# TripleCtrl.net
KiCad netlist of a schematic drawn in EAGLE
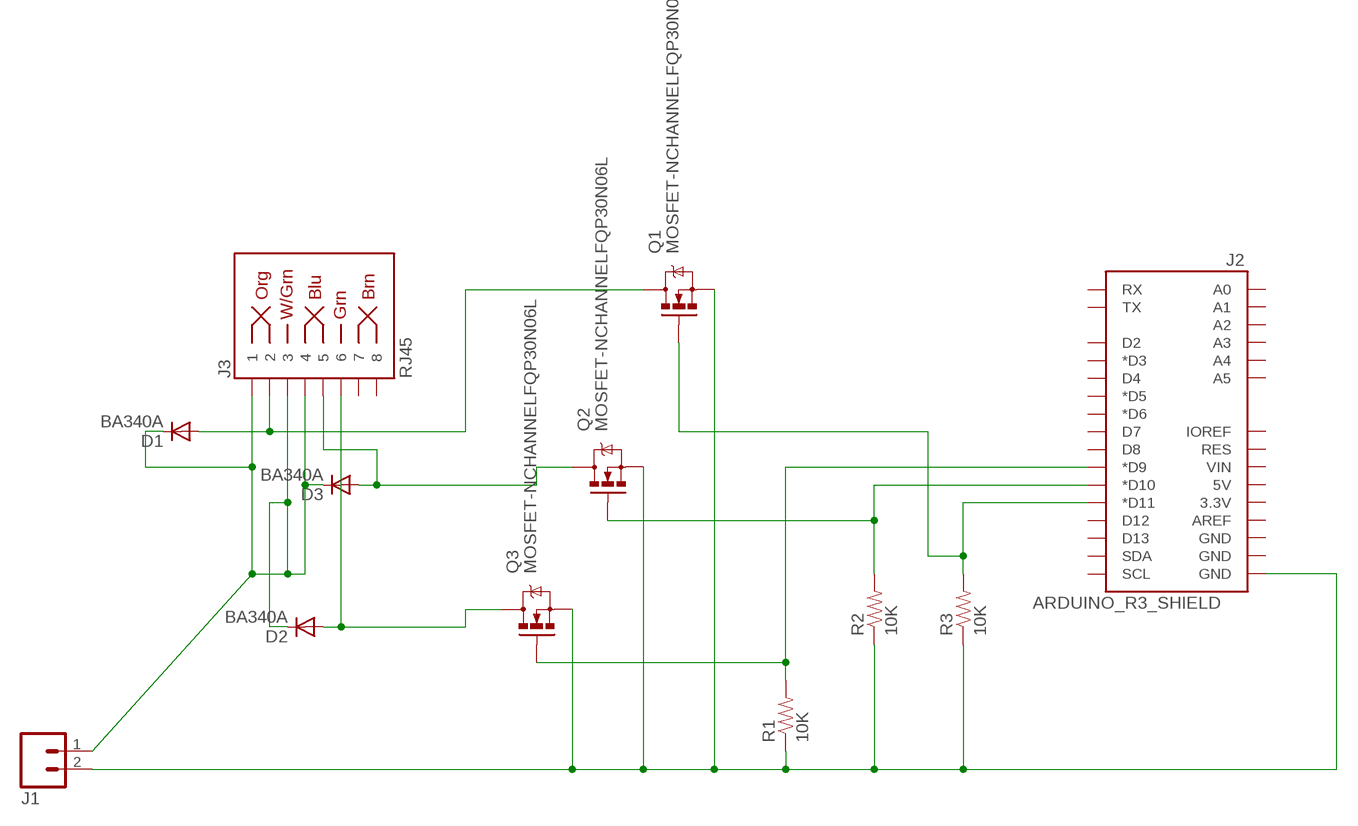
[diagram p0: schematic, sheet 1]

(export (version "E")
  (design (tool "Eeschema 10.0.6"))
  (components
    (comp (ref "D1")
      (value "BA340A")
      (footprint "eagle-import:DO41-10")
      (libsource (lib "eagle-import") (part "1N4004"))
    )
    (comp (ref "D2")
      (value "BA340A")
      (footprint "eagle-import:DO41-10")
      (libsource (lib "eagle-import") (part "1N4004"))
    )
    (comp (ref "D3")
      (value "BA340A")
      (footprint "eagle-import:DO41-10")
      (libsource (lib "eagle-import") (part "1N4004"))
    )
    (comp (ref "J1")
      (value "M025MM")
      (footprint "eagle-import:SCREWTERMINAL-5MM-2")
      (libsource (lib "eagle-import") (part "M025MM"))
    )
    (comp (ref "J2")
      (value "ARDUINO_R3_SHIELD")
      (footprint "eagle-import:UNO_R3_SHIELD")
      (libsource (lib "eagle-import") (part "ARDUINO_R3_SHIELD"))
    )
    (comp (ref "J3")
      (value "RJ45")
      (footprint "eagle-import:RJ45-8")
      (libsource (lib "eagle-import") (part "RJ45-8PTH"))
    )
    (comp (ref "Q1")
      (value "MOSFET-NCHANNELFQP30N06L")
      (footprint "eagle-import:TO220V")
      (libsource (lib "eagle-import") (part "MOSFET-NCHANNELFQP30N06L"))
    )
    (comp (ref "Q2")
      (value "MOSFET-NCHANNELFQP30N06L")
      (footprint "eagle-import:TO220V")
      (libsource (lib "eagle-import") (part "MOSFET-NCHANNELFQP30N06L"))
    )
    (comp (ref "Q3")
      (value "MOSFET-NCHANNELFQP30N06L")
      (footprint "eagle-import:TO220V")
      (libsource (lib "eagle-import") (part "MOSFET-NCHANNELFQP30N06L"))
    )
    (comp (ref "R1")
      (value "10K")
      (footprint "eagle-import:AXIAL-0.3-KIT")
      (libsource (lib "eagle-import") (part "10KOHM-1/6W-5%(PTH)KIT"))
    )
    (comp (ref "R2")
      (value "10K")
      (footprint "eagle-import:AXIAL-0.3-KIT")
      (libsource (lib "eagle-import") (part "10KOHM-1/6W-5%(PTH)KIT"))
    )
    (comp (ref "R3")
      (value "10K")
      (footprint "eagle-import:AXIAL-0.3-KIT")
      (libsource (lib "eagle-import") (part "10KOHM-1/6W-5%(PTH)KIT"))
    )
  )
  (nets
    (net (code "1") (name "Net-(D1-PadC)") (class "Default")
      (node (ref "D1") (pin "C") (pinfunction "C_C") (pintype "passive"))
      (node (ref "D2") (pin "C") (pinfunction "C_C") (pintype "passive"))
      (node (ref "D3") (pin "C") (pinfunction "C_C") (pintype "passive"))
      (node (ref "J1") (pin "1") (pinfunction "1_1") (pintype "passive"))
      (node (ref "J3") (pin "1") (pinfunction "1_1") (pintype "bidirectional"))
      (node (ref "J3") (pin "3") (pinfunction "3_3") (pintype "bidirectional"))
      (node (ref "J3") (pin "4") (pinfunction "4_4") (pintype "bidirectional"))
    )
    (net (code "2") (name "Net-(J2-*D9)") (class "Default")
      (node (ref "J2") (pin "D9") (pinfunction "*D9_D9") (pintype "bidirectional"))
      (node (ref "Q3") (pin "1") (pinfunction "G_1") (pintype "passive"))
      (node (ref "R1") (pin "P$2") (pinfunction "2_P$2") (pintype "passive"))
    )
    (net (code "3") (name "Net-(J2-*D10)") (class "Default")
      (node (ref "J2") (pin "D10") (pinfunction "*D10_D10") (pintype "bidirectional"))
      (node (ref "Q2") (pin "1") (pinfunction "G_1") (pintype "passive"))
      (node (ref "R2") (pin "P$2") (pinfunction "2_P$2") (pintype "passive"))
    )
    (net (code "4") (name "Net-(J2-*D11)") (class "Default")
      (node (ref "J2") (pin "D11") (pinfunction "*D11_D11") (pintype "bidirectional"))
      (node (ref "Q1") (pin "1") (pinfunction "G_1") (pintype "passive"))
      (node (ref "R3") (pin "P$2") (pinfunction "2_P$2") (pintype "passive"))
    )
    (net (code "5") (name "Net-(Q1-D)") (class "Default")
      (node (ref "D1") (pin "A") (pinfunction "A_A") (pintype "passive"))
      (node (ref "J3") (pin "2") (pinfunction "2_2") (pintype "bidirectional"))
      (node (ref "Q1") (pin "2") (pinfunction "D_2") (pintype "passive"))
    )
    (net (code "6") (name "Net-(Q1-S)") (class "Default")
      (node (ref "J1") (pin "2") (pinfunction "2_2") (pintype "passive"))
      (node (ref "J2") (pin "GND@0") (pinfunction "GND_GND@0") (pintype "bidirectional"))
      (node (ref "Q1") (pin "3") (pinfunction "S_3") (pintype "passive"))
      (node (ref "Q2") (pin "3") (pinfunction "S_3") (pintype "passive"))
      (node (ref "Q3") (pin "3") (pinfunction "S_3") (pintype "passive"))
      (node (ref "R1") (pin "P$1") (pinfunction "1_P$1") (pintype "passive"))
      (node (ref "R2") (pin "P$1") (pinfunction "1_P$1") (pintype "passive"))
      (node (ref "R3") (pin "P$1") (pinfunction "1_P$1") (pintype "passive"))
    )
    (net (code "7") (name "Net-(Q2-D)") (class "Default")
      (node (ref "D3") (pin "A") (pinfunction "A_A") (pintype "passive"))
      (node (ref "J3") (pin "5") (pinfunction "5_5") (pintype "bidirectional"))
      (node (ref "Q2") (pin "2") (pinfunction "D_2") (pintype "passive"))
    )
    (net (code "8") (name "Net-(Q3-D)") (class "Default")
      (node (ref "D2") (pin "A") (pinfunction "A_A") (pintype "passive"))
      (node (ref "J3") (pin "6") (pinfunction "6_6") (pintype "bidirectional"))
      (node (ref "Q3") (pin "2") (pinfunction "D_2") (pintype "passive"))
    )
    (net (code "9") (name "unconnected-(J2-*D3-PadD3)") (class "Default")
      (node (ref "J2") (pin "D3") (pinfunction "*D3_D3") (pintype "bidirectional"))
    )
    (net (code "10") (name "unconnected-(J2-*D5-PadD5)") (class "Default")
      (node (ref "J2") (pin "D5") (pinfunction "*D5_D5") (pintype "bidirectional"))
    )
    (net (code "11") (name "unconnected-(J2-*D6-PadD6)") (class "Default")
      (node (ref "J2") (pin "D6") (pinfunction "*D6_D6") (pintype "bidirectional"))
    )
    (net (code "12") (name "unconnected-(J2-GND-PadGND@1)") (class "Default")
      (node (ref "J2") (pin "GND@1") (pinfunction "GND_GND@1") (pintype "bidirectional"))
    )
    (net (code "13") (name "unconnected-(J2-GND-PadGND@2)") (class "Default")
      (node (ref "J2") (pin "GND@2") (pinfunction "GND_GND@2") (pintype "bidirectional"))
    )
    (net (code "14") (name "unconnected-(J2-Pad3.3V)") (class "Default")
      (node (ref "J2") (pin "3.3V") (pinfunction "3.3V_3.3V") (pintype "bidirectional"))
    )
    (net (code "15") (name "unconnected-(J2-Pad5V)") (class "Default")
      (node (ref "J2") (pin "5V") (pinfunction "5V_5V") (pintype "bidirectional"))
    )
    (net (code "16") (name "unconnected-(J2-PadA0)") (class "Default")
      (node (ref "J2") (pin "A0") (pinfunction "A0_A0") (pintype "bidirectional"))
    )
    (net (code "17") (name "unconnected-(J2-PadA1)") (class "Default")
      (node (ref "J2") (pin "A1") (pinfunction "A1_A1") (pintype "bidirectional"))
    )
    (net (code "18") (name "unconnected-(J2-PadA2)") (class "Default")
      (node (ref "J2") (pin "A2") (pinfunction "A2_A2") (pintype "bidirectional"))
    )
    (net (code "19") (name "unconnected-(J2-PadA3)") (class "Default")
      (node (ref "J2") (pin "A3") (pinfunction "A3_A3") (pintype "bidirectional"))
    )
    (net (code "20") (name "unconnected-(J2-PadA4)") (class "Default")
      (node (ref "J2") (pin "A4") (pinfunction "A4_A4") (pintype "bidirectional"))
    )
    (net (code "21") (name "unconnected-(J2-PadA5)") (class "Default")
      (node (ref "J2") (pin "A5") (pinfunction "A5_A5") (pintype "bidirectional"))
    )
    (net (code "22") (name "unconnected-(J2-PadAREF)") (class "Default")
      (node (ref "J2") (pin "AREF") (pinfunction "AREF_AREF") (pintype "bidirectional"))
    )
    (net (code "23") (name "unconnected-(J2-PadD2)") (class "Default")
      (node (ref "J2") (pin "D2") (pinfunction "D2_D2") (pintype "bidirectional"))
    )
    (net (code "24") (name "unconnected-(J2-PadD4)") (class "Default")
      (node (ref "J2") (pin "D4") (pinfunction "D4_D4") (pintype "bidirectional"))
    )
    (net (code "25") (name "unconnected-(J2-PadD7)") (class "Default")
      (node (ref "J2") (pin "D7") (pinfunction "D7_D7") (pintype "bidirectional"))
    )
    (net (code "26") (name "unconnected-(J2-PadD8)") (class "Default")
      (node (ref "J2") (pin "D8") (pinfunction "D8_D8") (pintype "bidirectional"))
    )
    (net (code "27") (name "unconnected-(J2-PadD12)") (class "Default")
      (node (ref "J2") (pin "D12") (pinfunction "D12_D12") (pintype "bidirectional"))
    )
    (net (code "28") (name "unconnected-(J2-PadD13)") (class "Default")
      (node (ref "J2") (pin "D13") (pinfunction "D13_D13") (pintype "bidirectional"))
    )
    (net (code "29") (name "unconnected-(J2-PadIOREF)") (class "Default")
      (node (ref "J2") (pin "IOREF") (pinfunction "IOREF_IOREF") (pintype "bidirectional"))
    )
    (net (code "30") (name "unconnected-(J2-PadRES)") (class "Default")
      (node (ref "J2") (pin "RES") (pinfunction "RES_RES") (pintype "bidirectional"))
    )
    (net (code "31") (name "unconnected-(J2-PadRX)") (class "Default")
      (node (ref "J2") (pin "RX") (pinfunction "RX_RX") (pintype "bidirectional"))
    )
    (net (code "32") (name "unconnected-(J2-PadSCL)") (class "Default")
      (node (ref "J2") (pin "SCL") (pinfunction "SCL_SCL") (pintype "bidirectional"))
    )
    (net (code "33") (name "unconnected-(J2-PadSDA)") (class "Default")
      (node (ref "J2") (pin "SDA") (pinfunction "SDA_SDA") (pintype "bidirectional"))
    )
    (net (code "34") (name "unconnected-(J2-PadTX)") (class "Default")
      (node (ref "J2") (pin "TX") (pinfunction "TX_TX") (pintype "bidirectional"))
    )
    (net (code "35") (name "unconnected-(J2-PadVIN)") (class "Default")
      (node (ref "J2") (pin "VIN") (pinfunction "VIN_VIN") (pintype "bidirectional"))
    )
    (net (code "36") (name "unconnected-(J3-Pad7)") (class "Default")
      (node (ref "J3") (pin "7") (pinfunction "7_7") (pintype "bidirectional"))
    )
    (net (code "37") (name "unconnected-(J3-Pad8)") (class "Default")
      (node (ref "J3") (pin "8") (pinfunction "8_8") (pintype "bidirectional"))
    )
  )
)
